# Schematic.net
KiCad netlist of a schematic drawn in Altium Designer
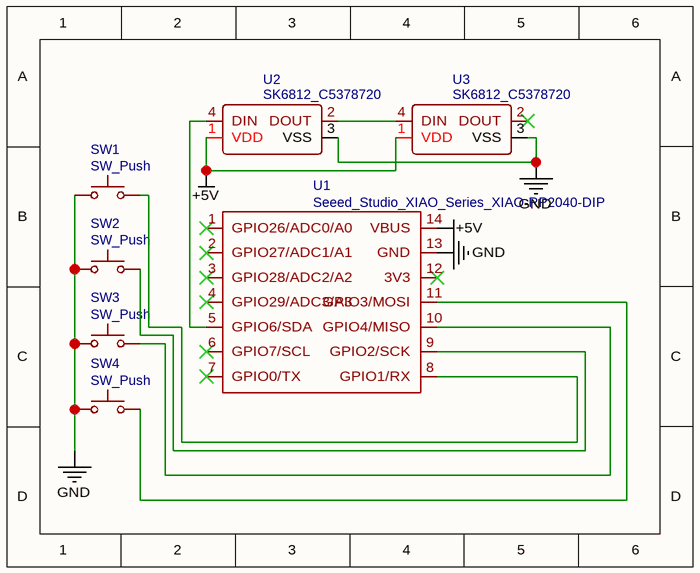
[diagram p0: Schematic.schdoc]

(export (version "E")
  (design (tool "Eeschema 10.0.6"))
  (components
    (comp (ref "SW1")
      (value "SW_Push")
      (fields (field (name "CONTRIBUTOR") "KiCAD"))
      (libsource (lib "altium-import") (part "root_0_SW_Push_"))
    )
    (comp (ref "SW2")
      (value "SW_Push")
      (fields (field (name "CONTRIBUTOR") "KiCAD"))
      (libsource (lib "altium-import") (part "root_0_SW_Push_"))
    )
    (comp (ref "SW3")
      (value "SW_Push")
      (fields (field (name "CONTRIBUTOR") "KiCAD"))
      (libsource (lib "altium-import") (part "root_0_SW_Push_"))
    )
    (comp (ref "SW4")
      (value "SW_Push")
      (fields (field (name "CONTRIBUTOR") "KiCAD"))
      (libsource (lib "altium-import") (part "root_0_SW_Push_"))
    )
    (comp (ref "U1")
      (value "Seeed_Studio_XIAO_Series_XIAO-RP2040-DIP")
      (fields (field (name "CONTRIBUTOR") "ryantaw"))
      (libsource (lib "altium-import") (part "root_0_Seeed_Studio_XIAO_Series_XIAO-RP2040-DIP_"))
    )
    (comp (ref "U2")
      (value "SK6812_C5378720")
      (fields
        (field (name "MANUFACTURER") "欧思科光电")
        (field (name "MANUFACTURER PART") "SK6812")
        (field (name "CONTRIBUTOR") "lcsc")
      )
      (libsource (lib "altium-import") (part "root_0_SK6812_C5378720_"))
    )
    (comp (ref "U3")
      (value "SK6812_C5378720")
      (fields
        (field (name "MANUFACTURER") "欧思科光电")
        (field (name "MANUFACTURER PART") "SK6812")
        (field (name "CONTRIBUTOR") "lcsc")
      )
      (libsource (lib "altium-import") (part "root_0_SK6812_C5378720_"))
    )
  )
  (nets
    (net (code "1") (name "+5V") (class "Default")
      (node (ref "U1") (pin "14") (pinfunction "VBUS_14") (pintype "passive"))
      (node (ref "U2") (pin "1") (pinfunction "VDD_1") (pintype "passive"))
      (node (ref "U3") (pin "1") (pinfunction "VDD_1") (pintype "passive"))
    )
    (net (code "2") (name "GND") (class "Default")
      (node (ref "SW1") (pin "1") (pinfunction "1_1") (pintype "passive"))
      (node (ref "SW2") (pin "1") (pinfunction "1_1") (pintype "passive"))
      (node (ref "SW3") (pin "1") (pinfunction "1_1") (pintype "passive"))
      (node (ref "SW4") (pin "1") (pinfunction "1_1") (pintype "passive"))
      (node (ref "U1") (pin "13") (pinfunction "GND_13") (pintype "passive"))
      (node (ref "U2") (pin "3") (pinfunction "VSS_3") (pintype "passive"))
      (node (ref "U3") (pin "3") (pinfunction "VSS_3") (pintype "passive"))
    )
    (net (code "3") (name "Net-(U1-GPIO1{slash}RX)") (class "Default")
      (node (ref "SW1") (pin "2") (pinfunction "2_2") (pintype "passive"))
      (node (ref "U1") (pin "8") (pinfunction "GPIO1/RX_8") (pintype "passive"))
    )
    (net (code "4") (name "Net-(U1-GPIO2{slash}SCK)") (class "Default")
      (node (ref "SW2") (pin "2") (pinfunction "2_2") (pintype "passive"))
      (node (ref "U1") (pin "9") (pinfunction "GPIO2/SCK_9") (pintype "passive"))
    )
    (net (code "5") (name "Net-(U1-GPIO3{slash}MOSI)") (class "Default")
      (node (ref "SW4") (pin "2") (pinfunction "2_2") (pintype "passive"))
      (node (ref "U1") (pin "11") (pinfunction "GPIO3/MOSI_11") (pintype "passive"))
    )
    (net (code "6") (name "Net-(U1-GPIO4{slash}MISO)") (class "Default")
      (node (ref "SW3") (pin "2") (pinfunction "2_2") (pintype "passive"))
      (node (ref "U1") (pin "10") (pinfunction "GPIO4/MISO_10") (pintype "passive"))
    )
    (net (code "7") (name "Net-(U1-GPIO6{slash}SDA)") (class "Default")
      (node (ref "U1") (pin "5") (pinfunction "GPIO6/SDA_5") (pintype "passive"))
      (node (ref "U2") (pin "4") (pinfunction "DIN_4") (pintype "passive"))
    )
    (net (code "8") (name "Net-(U2-DOUT)") (class "Default")
      (node (ref "U2") (pin "2") (pinfunction "DOUT_2") (pintype "passive"))
      (node (ref "U3") (pin "4") (pinfunction "DIN_4") (pintype "passive"))
    )
    (net (code "9") (name "unconnected-(U1-3V3-Pad12)") (class "Default")
      (node (ref "U1") (pin "12") (pinfunction "3V3_12") (pintype "passive+no_connect"))
    )
    (net (code "10") (name "unconnected-(U1-GPIO0{slash}TX-Pad7)") (class "Default")
      (node (ref "U1") (pin "7") (pinfunction "GPIO0/TX_7") (pintype "passive+no_connect"))
    )
    (net (code "11") (name "unconnected-(U1-GPIO7{slash}SCL-Pad6)") (class "Default")
      (node (ref "U1") (pin "6") (pinfunction "GPIO7/SCL_6") (pintype "passive+no_connect"))
    )
    (net (code "12") (name "unconnected-(U1-GPIO26{slash}ADC0{slash}A0-Pad1)") (class "Default")
      (node (ref "U1") (pin "1") (pinfunction "GPIO26/ADC0/A0_1") (pintype "passive+no_connect"))
    )
    (net (code "13") (name "unconnected-(U1-GPIO27{slash}ADC1{slash}A1-Pad2)") (class "Default")
      (node (ref "U1") (pin "2") (pinfunction "GPIO27/ADC1/A1_2") (pintype "passive+no_connect"))
    )
    (net (code "14") (name "unconnected-(U1-GPIO28{slash}ADC2{slash}A2-Pad3)") (class "Default")
      (node (ref "U1") (pin "3") (pinfunction "GPIO28/ADC2/A2_3") (pintype "passive+no_connect"))
    )
    (net (code "15") (name "unconnected-(U1-GPIO29{slash}ADC3{slash}A3-Pad4)") (class "Default")
      (node (ref "U1") (pin "4") (pinfunction "GPIO29/ADC3/A3_4") (pintype "passive+no_connect"))
    )
    (net (code "16") (name "unconnected-(U3-DOUT-Pad2)") (class "Default")
      (node (ref "U3") (pin "2") (pinfunction "DOUT_2") (pintype "passive+no_connect"))
    )
  )
)
